# Digital_Clock_SCH_4_0.net
KiCad netlist of a schematic drawn in Altium Designer
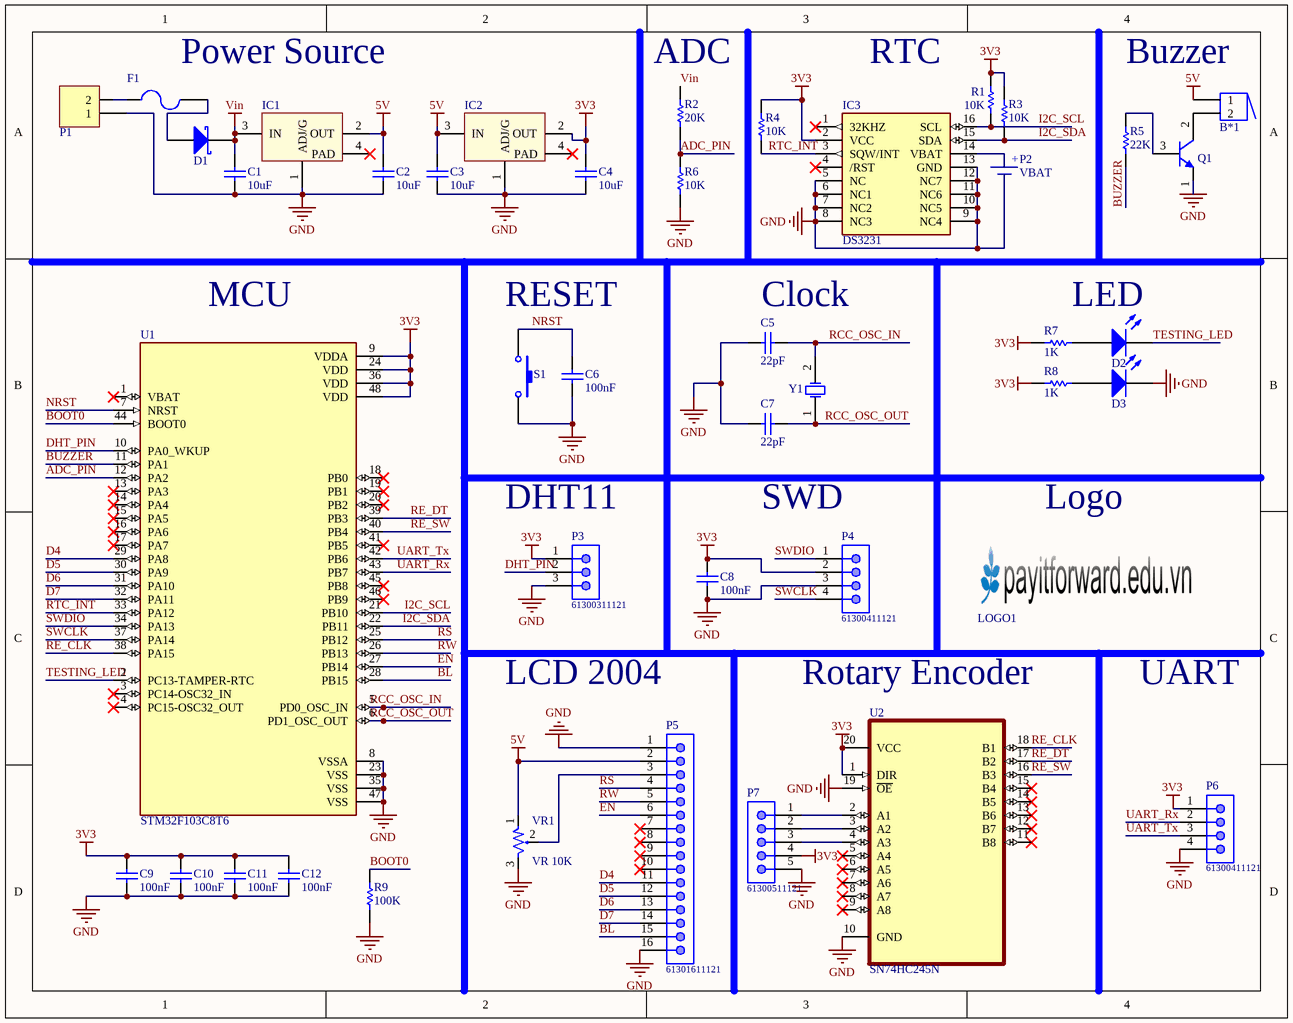
[diagram p0: Digital_Clock_SCH_4.0.SchDoc]

(export (version "E")
  (design (tool "Eeschema 10.0.6"))
  (components
    (comp (ref "B*1") (value "Buzzer") (footprint "BUZZER") (libsource (lib "PIF_Library") (part "Buzzer")))
    (comp (ref "C1")
      (value "10uF")
      (footprint "CAP-SM-0805")
      (description "Capacitor")
      (fields (field (name "Comment") "Cap Non-Pol SMD"))
      (libsource (lib "PIF_Library") (part "Cap Non-Pol SMD"))
    )
    (comp (ref "C2")
      (value "10uF")
      (footprint "CAP-SM-0805")
      (description "Capacitor")
      (fields (field (name "Comment") "Cap Non-Pol SMD"))
      (libsource (lib "PIF_Library") (part "Cap Non-Pol SMD"))
    )
    (comp (ref "C3")
      (value "10uF")
      (footprint "CAP-SM-0805")
      (description "Capacitor")
      (fields (field (name "Comment") "Cap Non-Pol SMD"))
      (libsource (lib "PIF_Library") (part "Cap Non-Pol SMD"))
    )
    (comp (ref "C4")
      (value "10uF")
      (footprint "CAP-SM-0805")
      (description "Capacitor")
      (fields (field (name "Comment") "Cap Non-Pol SMD"))
      (libsource (lib "PIF_Library") (part "Cap Non-Pol SMD"))
    )
    (comp (ref "C5")
      (value "22pF")
      (footprint "CAP-SM-0603")
      (description "Capacitor")
      (fields (field (name "Comment") "Cap Non-Pol SMD"))
      (libsource (lib "PIF_Library") (part "Cap Non-Pol SMD"))
    )
    (comp (ref "C6")
      (value "100nF")
      (footprint "CAP-SM-0603")
      (description "Capacitor")
      (fields (field (name "Comment") "Cap Non-Pol SMD"))
      (libsource (lib "PIF_Library") (part "Cap Non-Pol SMD"))
    )
    (comp (ref "C7")
      (value "22pF")
      (footprint "CAP-SM-0603")
      (description "Capacitor")
      (fields (field (name "Comment") "Cap Non-Pol SMD"))
      (libsource (lib "PIF_Library") (part "Cap Non-Pol SMD"))
    )
    (comp (ref "C8")
      (value "100nF")
      (footprint "CAP-SM-0603")
      (description "Capacitor")
      (fields (field (name "Comment") "Cap Non-Pol SMD"))
      (libsource (lib "PIF_Library") (part "Cap Non-Pol SMD"))
    )
    (comp (ref "C9")
      (value "100nF")
      (footprint "CAP-SM-0603")
      (description "Capacitor")
      (fields (field (name "Comment") "Cap Non-Pol SMD"))
      (libsource (lib "PIF_Library") (part "Cap Non-Pol SMD"))
    )
    (comp (ref "C10")
      (value "100nF")
      (footprint "CAP-SM-0603")
      (description "Capacitor")
      (fields (field (name "Comment") "Cap Non-Pol SMD"))
      (libsource (lib "PIF_Library") (part "Cap Non-Pol SMD"))
    )
    (comp (ref "C11")
      (value "100nF")
      (footprint "CAP-SM-0603")
      (description "Capacitor")
      (fields (field (name "Comment") "Cap Non-Pol SMD"))
      (libsource (lib "PIF_Library") (part "Cap Non-Pol SMD"))
    )
    (comp (ref "C12")
      (value "100nF")
      (footprint "CAP-SM-0603")
      (description "Capacitor")
      (fields (field (name "Comment") "Cap Non-Pol SMD"))
      (libsource (lib "PIF_Library") (part "Cap Non-Pol SMD"))
    )
    (comp (ref "D1")
      (value "D Schottky")
      (footprint "SS34")
      (description "Schottky Diode")
      (fields (field (name "PUBLISHER") "Altium Limited"))
      (libsource (lib "PIF_Library") (part "D Schottky"))
    )
    (comp (ref "D2")
      (value "LED SMD")
      (footprint "LED_0805_Blue")
      (description "LED")
      (libsource (lib "PIF_Library") (part "LED SMD"))
    )
    (comp (ref "D3")
      (value "LED SMD")
      (footprint "LED_0805_Blue")
      (description "LED")
      (libsource (lib "PIF_Library") (part "LED SMD"))
    )
    (comp (ref "F1") (value "Fuse") (footprint "FUSE SMD") (libsource (lib "PIF_Library") (part "Fuse")))
    (comp (ref "IC1")
      (value "LM1117")
      (footprint "SOT223-4N")
      (description "Available in 1.8V, 2.5V, 2.85V, 3.3V, 5V, and  Adjustable Versions")
      (libsource (lib "PIF_Library") (part "LM1117"))
    )
    (comp (ref "IC2")
      (value "LM1117")
      (footprint "SOT223-4N")
      (description "Available in 1.8V, 2.5V, 2.85V, 3.3V, 5V, and  Adjustable Versions")
      (libsource (lib "PIF_Library") (part "LM1117"))
    )
    (comp (ref "IC3") (value "DS3231") (footprint "SO16W") (libsource (lib "DS3231") (part "DS3231")))
    (comp (ref "LOGO1")
      (value "LOGO PIF")
      (footprint "PIF LOGO BIG SSTOP")
      (libsource (lib "PIF_Library") (part "LOGO PIF"))
    )
    (comp (ref "P1")
      (value "Domino 2")
      (footprint "DOMINO SMALL 2")
      (description "Domino, 2-Pin")
      (fields (field (name "PUBLISHER") "Altium Limited"))
      (libsource (lib "PIF_Library") (part "Domino 2"))
    )
    (comp (ref "P2")
      (value "VBAT")
      (footprint "VBAT CR2030")
      (description "CR2032")
      (fields
        (field (name "MANUFACTURER") "DANTONA INDUSTRIES")
        (field (name "MANUFACTURER PART NUMBER") "CR2032 SANYO")
      )
      (libsource (lib "DeltaCross_Lib") (part "VBAT CR2032"))
    )
    (comp (ref "P3")
      (value "61300311121")
      (footprint "61300311121")
      (description "WR-PHD Pin Header, THT, pitch 2.54mm, Single Row, Vertical, 3p")
      (fields (field (name "MANUFACTURER") "Wurth Elektronik"))
      (libsource (lib "Altium_WR-PHD (rev20a)") (part "61300311121"))
    )
    (comp (ref "P4")
      (value "61300411121")
      (footprint "61300411121")
      (description "WR-PHD Pin Header, THT, pitch 2.54mm, Single Row, Vertical, 4p")
      (fields (field (name "MANUFACTURER") "Wurth Elektronik"))
      (libsource (lib "Altium_WR-PHD (rev20a)") (part "61300411121"))
    )
    (comp (ref "P5")
      (value "61301611121")
      (footprint "61301611121")
      (description "WR-PHD Pin Header, THT, pitch 2.54mm, Single Row, Vertical, 16p")
      (fields (field (name "MANUFACTURER") "Wurth Elektronik"))
      (libsource (lib "Altium_WR-PHD (rev20a)") (part "61301611121"))
    )
    (comp (ref "P6")
      (value "61300411121")
      (footprint "61300411121")
      (description "WR-PHD Pin Header, THT, pitch 2.54mm, Single Row, Vertical, 4p")
      (fields (field (name "MANUFACTURER") "Wurth Elektronik"))
      (libsource (lib "Altium_WR-PHD (rev20a)") (part "61300411121"))
    )
    (comp (ref "P7")
      (value "61300511121")
      (footprint "61300511121")
      (description "WR-PHD Pin Header, THT, pitch 2.54mm, Single Row, Vertical, 5p")
      (fields (field (name "MANUFACTURER") "Wurth Elektronik"))
      (libsource (lib "Altium_WR-PHD (rev20a)") (part "61300511121"))
    )
    (comp (ref "Q1")
      (value "C1815")
      (footprint "SOT23B")
      (description "NPN Bipolar Transistor")
      (libsource (lib "PIF_Library") (part "C1815"))
    )
    (comp (ref "R1")
      (value "10K")
      (footprint "RES-SM-0603")
      (description "Resistor")
      (fields (field (name "Comment") "RESISTOR SMD"))
      (libsource (lib "PIF_Library") (part "RESISTOR SMD"))
    )
    (comp (ref "R2")
      (value "20K")
      (footprint "RES-SM-0603")
      (description "Resistor")
      (fields (field (name "Comment") "RESISTOR SMD"))
      (libsource (lib "PIF_Library") (part "RESISTOR SMD"))
    )
    (comp (ref "R3")
      (value "10K")
      (footprint "RES-SM-0603")
      (description "Resistor")
      (fields (field (name "Comment") "RESISTOR SMD"))
      (libsource (lib "PIF_Library") (part "RESISTOR SMD"))
    )
    (comp (ref "R4")
      (value "10K")
      (footprint "RES-SM-0603")
      (description "Resistor")
      (fields (field (name "Comment") "RESISTOR SMD"))
      (libsource (lib "PIF_Library") (part "RESISTOR SMD"))
    )
    (comp (ref "R5")
      (value "22K")
      (footprint "RES-SM-0603")
      (description "Resistor")
      (fields (field (name "Comment") "RESISTOR SMD"))
      (libsource (lib "PIF_Library") (part "RESISTOR SMD"))
    )
    (comp (ref "R6")
      (value "10K")
      (footprint "RES-SM-0603")
      (description "Resistor")
      (fields (field (name "Comment") "RESISTOR SMD"))
      (libsource (lib "PIF_Library") (part "RESISTOR SMD"))
    )
    (comp (ref "R7")
      (value "1K")
      (footprint "RES-SM-0603")
      (description "Resistor")
      (fields (field (name "Comment") "RESISTOR SMD"))
      (libsource (lib "PIF_Library") (part "RESISTOR SMD"))
    )
    (comp (ref "R8")
      (value "1K")
      (footprint "RES-SM-0603")
      (description "Resistor")
      (fields (field (name "Comment") "RESISTOR SMD"))
      (libsource (lib "PIF_Library") (part "RESISTOR SMD"))
    )
    (comp (ref "R9")
      (value "100K")
      (footprint "RES-SM-0603")
      (description "Resistor")
      (fields (field (name "Comment") "RESISTOR SMD"))
      (libsource (lib "PIF_Library") (part "RESISTOR SMD"))
    )
    (comp (ref "S1")
      (value "Tact SW - 2Pin")
      (footprint "SW-SMD")
      (description "Switch button 2 pin")
      (libsource (lib "PIF_Library") (part "Tact SW - 2Pin"))
    )
    (comp (ref "U1")
      (value "STM32F103C8T6")
      (footprint "QFP50P900X900X160-48N")
      (libsource (lib "STM32F103C8T6") (part "STM32F103C8T6"))
    )
    (comp (ref "U2")
      (value "SN74HC245N")
      (footprint "DIP254P762X508-20")
      (description "Octal Bus Transceivers With 3-State Outputs 20-PDIP -40 to 85")
      (fields (field (name "MF") "Texas Instruments"))
      (libsource (lib "SN74HC245N") (part "SN74HC245N"))
    )
    (comp (ref "VR1")
      (value "VR 10K")
      (footprint "Varistor 1")
      (description "Var Resistor")
      (fields (field (name "Comment") "10K"))
      (libsource (lib "PIF_Library") (part "Var Resistor"))
    )
    (comp (ref "Y1")
      (value "XTAL")
      (footprint "XT2")
      (description "Crystal Oscillator")
      (fields (field (name "PUBLISHER") "Altium Limited"))
      (libsource (lib "PIF_Library") (part "XTAL"))
    )
  )
  (nets
    (net (code "1") (name "/ADC_PIN") (class "Default")
      (node (ref "R2") (pin "1") (pinfunction "1_1") (pintype "passive"))
      (node (ref "R6") (pin "2") (pinfunction "2_2") (pintype "passive"))
      (node (ref "U1") (pin "12") (pinfunction "PA2_12") (pintype "bidirectional"))
    )
    (net (code "2") (name "/BL") (class "Default")
      (node (ref "P5") (pin "15") (pinfunction "15_15") (pintype "passive"))
      (node (ref "U1") (pin "28") (pinfunction "PB15_28") (pintype "bidirectional"))
    )
    (net (code "3") (name "/BOOT0") (class "Default")
      (node (ref "R9") (pin "2") (pinfunction "2_2") (pintype "passive"))
      (node (ref "U1") (pin "44") (pinfunction "BOOT0_44") (pintype "input"))
    )
    (net (code "4") (name "/BUZZER") (class "Default")
      (node (ref "R5") (pin "1") (pinfunction "1_1") (pintype "passive"))
      (node (ref "U1") (pin "11") (pinfunction "PA1_11") (pintype "bidirectional"))
    )
    (net (code "5") (name "/D4") (class "Default")
      (node (ref "P5") (pin "11") (pinfunction "11_11") (pintype "passive"))
      (node (ref "U1") (pin "29") (pinfunction "PA8_29") (pintype "bidirectional"))
    )
    (net (code "6") (name "/D5") (class "Default")
      (node (ref "P5") (pin "12") (pinfunction "12_12") (pintype "passive"))
      (node (ref "U1") (pin "30") (pinfunction "PA9_30") (pintype "bidirectional"))
    )
    (net (code "7") (name "/D6") (class "Default")
      (node (ref "P5") (pin "13") (pinfunction "13_13") (pintype "passive"))
      (node (ref "U1") (pin "31") (pinfunction "PA10_31") (pintype "bidirectional"))
    )
    (net (code "8") (name "/D7") (class "Default")
      (node (ref "P5") (pin "14") (pinfunction "14_14") (pintype "passive"))
      (node (ref "U1") (pin "32") (pinfunction "PA11_32") (pintype "bidirectional"))
    )
    (net (code "9") (name "/DHT_PIN") (class "Default")
      (node (ref "P3") (pin "2") (pinfunction "2_2") (pintype "passive"))
      (node (ref "U1") (pin "10") (pinfunction "PA0_WKUP_10") (pintype "bidirectional"))
    )
    (net (code "10") (name "/EN") (class "Default")
      (node (ref "P5") (pin "6") (pinfunction "6_6") (pintype "passive"))
      (node (ref "U1") (pin "27") (pinfunction "PB14_27") (pintype "bidirectional"))
    )
    (net (code "11") (name "/I2C_SCL") (class "Default")
      (node (ref "IC3") (pin "16") (pinfunction "SCL_16") (pintype "bidirectional"))
      (node (ref "R1") (pin "1") (pinfunction "1_1") (pintype "passive"))
      (node (ref "U1") (pin "21") (pinfunction "PB10_21") (pintype "bidirectional"))
    )
    (net (code "12") (name "/I2C_SDA") (class "Default")
      (node (ref "IC3") (pin "15") (pinfunction "SDA_15") (pintype "bidirectional"))
      (node (ref "R3") (pin "1") (pinfunction "1_1") (pintype "passive"))
      (node (ref "U1") (pin "22") (pinfunction "PB11_22") (pintype "bidirectional"))
    )
    (net (code "13") (name "/NRST") (class "Default")
      (node (ref "C6") (pin "2") (pinfunction "2_2") (pintype "passive"))
      (node (ref "S1") (pin "1") (pinfunction "1_1") (pintype "passive"))
      (node (ref "U1") (pin "7") (pinfunction "NRST_7") (pintype "input"))
    )
    (net (code "14") (name "/RCC_OSC_IN") (class "Default")
      (node (ref "C5") (pin "2") (pinfunction "2_2") (pintype "passive"))
      (node (ref "U1") (pin "5") (pinfunction "PD0_OSC_IN_5") (pintype "bidirectional"))
      (node (ref "Y1") (pin "2") (pinfunction "OSC2_2") (pintype "passive"))
    )
    (net (code "15") (name "/RCC_OSC_OUT") (class "Default")
      (node (ref "C7") (pin "1") (pinfunction "1_1") (pintype "passive"))
      (node (ref "U1") (pin "6") (pinfunction "PD1_OSC_OUT_6") (pintype "bidirectional"))
      (node (ref "Y1") (pin "1") (pinfunction "OSC1_1") (pintype "passive"))
    )
    (net (code "16") (name "/RE_CLK") (class "Default")
      (node (ref "U1") (pin "38") (pinfunction "PA15_38") (pintype "bidirectional"))
      (node (ref "U2") (pin "18") (pinfunction "B1_18") (pintype "bidirectional"))
    )
    (net (code "17") (name "/RE_DT") (class "Default")
      (node (ref "U1") (pin "39") (pinfunction "PB3_39") (pintype "bidirectional"))
      (node (ref "U2") (pin "17") (pinfunction "B2_17") (pintype "bidirectional"))
    )
    (net (code "18") (name "/RE_SW") (class "Default")
      (node (ref "U1") (pin "40") (pinfunction "PB4_40") (pintype "bidirectional"))
      (node (ref "U2") (pin "16") (pinfunction "B3_16") (pintype "bidirectional"))
    )
    (net (code "19") (name "/RS") (class "Default")
      (node (ref "P5") (pin "4") (pinfunction "4_4") (pintype "passive"))
      (node (ref "U1") (pin "25") (pinfunction "PB12_25") (pintype "bidirectional"))
    )
    (net (code "20") (name "/RTC_INT") (class "Default")
      (node (ref "IC3") (pin "3") (pinfunction "SQW/INT_3") (pintype "output"))
      (node (ref "R4") (pin "1") (pinfunction "1_1") (pintype "passive"))
      (node (ref "U1") (pin "33") (pinfunction "PA12_33") (pintype "bidirectional"))
    )
    (net (code "21") (name "/RW") (class "Default")
      (node (ref "P5") (pin "5") (pinfunction "5_5") (pintype "passive"))
      (node (ref "U1") (pin "26") (pinfunction "PB13_26") (pintype "bidirectional"))
    )
    (net (code "22") (name "/SWCLK") (class "Default")
      (node (ref "P4") (pin "4") (pinfunction "4_4") (pintype "passive"))
      (node (ref "U1") (pin "37") (pinfunction "PA14_37") (pintype "bidirectional"))
    )
    (net (code "23") (name "/SWDIO") (class "Default")
      (node (ref "P4") (pin "1") (pinfunction "1_1") (pintype "passive"))
      (node (ref "U1") (pin "34") (pinfunction "PA13_34") (pintype "bidirectional"))
    )
    (net (code "24") (name "/TESTING_LED") (class "Default")
      (node (ref "D2") (pin "2") (pinfunction "K_2") (pintype "passive"))
      (node (ref "U1") (pin "2") (pinfunction "PC13-TAMPER-RTC_2") (pintype "bidirectional"))
    )
    (net (code "25") (name "/UART_Rx") (class "Default")
      (node (ref "P6") (pin "2") (pinfunction "2_2") (pintype "passive"))
      (node (ref "U1") (pin "43") (pinfunction "PB7_43") (pintype "bidirectional"))
    )
    (net (code "26") (name "/UART_Tx") (class "Default")
      (node (ref "P6") (pin "3") (pinfunction "3_3") (pintype "passive"))
      (node (ref "U1") (pin "42") (pinfunction "PB6_42") (pintype "bidirectional"))
    )
    (net (code "27") (name "3V3") (class "Default")
      (node (ref "C10") (pin "2") (pinfunction "2_2") (pintype "passive"))
      (node (ref "C11") (pin "2") (pinfunction "2_2") (pintype "passive"))
      (node (ref "C12") (pin "2") (pinfunction "2_2") (pintype "passive"))
      (node (ref "C4") (pin "2") (pinfunction "2_2") (pintype "passive"))
      (node (ref "C8") (pin "2") (pinfunction "2_2") (pintype "passive"))
      (node (ref "C9") (pin "2") (pinfunction "2_2") (pintype "passive"))
      (node (ref "IC2") (pin "2") (pinfunction "OUT_2") (pintype "passive"))
      (node (ref "IC3") (pin "2") (pinfunction "VCC_2") (pintype "power_in"))
      (node (ref "P3") (pin "1") (pinfunction "1_1") (pintype "passive"))
      (node (ref "P4") (pin "2") (pinfunction "2_2") (pintype "passive"))
      (node (ref "P6") (pin "1") (pinfunction "1_1") (pintype "passive"))
      (node (ref "P7") (pin "4") (pinfunction "4_4") (pintype "passive"))
      (node (ref "R1") (pin "2") (pinfunction "2_2") (pintype "passive"))
      (node (ref "R3") (pin "2") (pinfunction "2_2") (pintype "passive"))
      (node (ref "R4") (pin "2") (pinfunction "2_2") (pintype "passive"))
      (node (ref "R7") (pin "1") (pinfunction "1_1") (pintype "passive"))
      (node (ref "R8") (pin "1") (pinfunction "1_1") (pintype "passive"))
      (node (ref "U1") (pin "24") (pinfunction "VDD_24") (pintype "power_in"))
      (node (ref "U1") (pin "36") (pinfunction "VDD_36") (pintype "power_in"))
      (node (ref "U1") (pin "48") (pinfunction "VDD_48") (pintype "power_in"))
      (node (ref "U1") (pin "9") (pinfunction "VDDA_9") (pintype "power_in"))
      (node (ref "U2") (pin "1") (pinfunction "DIR_1") (pintype "input"))
      (node (ref "U2") (pin "20") (pinfunction "VCC_20") (pintype "power_in"))
    )
    (net (code "28") (name "5V") (class "Default")
      (node (ref "B*1") (pin "1") (pinfunction "1_1") (pintype "passive"))
      (node (ref "C2") (pin "2") (pinfunction "2_2") (pintype "passive"))
      (node (ref "C3") (pin "2") (pinfunction "2_2") (pintype "passive"))
      (node (ref "IC1") (pin "2") (pinfunction "OUT_2") (pintype "passive"))
      (node (ref "IC2") (pin "3") (pinfunction "IN_3") (pintype "passive"))
      (node (ref "P5") (pin "2") (pinfunction "2_2") (pintype "passive"))
      (node (ref "VR1") (pin "1") (pinfunction "1_1") (pintype "passive"))
    )
    (net (code "29") (name "GND") (class "Default")
      (node (ref "C1") (pin "1") (pinfunction "1_1") (pintype "passive"))
      (node (ref "C10") (pin "1") (pinfunction "1_1") (pintype "passive"))
      (node (ref "C11") (pin "1") (pinfunction "1_1") (pintype "passive"))
      (node (ref "C12") (pin "1") (pinfunction "1_1") (pintype "passive"))
      (node (ref "C2") (pin "1") (pinfunction "1_1") (pintype "passive"))
      (node (ref "C3") (pin "1") (pinfunction "1_1") (pintype "passive"))
      (node (ref "C4") (pin "1") (pinfunction "1_1") (pintype "passive"))
      (node (ref "C5") (pin "1") (pinfunction "1_1") (pintype "passive"))
      (node (ref "C6") (pin "1") (pinfunction "1_1") (pintype "passive"))
      (node (ref "C7") (pin "2") (pinfunction "2_2") (pintype "passive"))
      (node (ref "C8") (pin "1") (pinfunction "1_1") (pintype "passive"))
      (node (ref "C9") (pin "1") (pinfunction "1_1") (pintype "passive"))
      (node (ref "D3") (pin "2") (pinfunction "K_2") (pintype "passive"))
      (node (ref "IC1") (pin "1") (pinfunction "ADJ/G_1") (pintype "passive"))
      (node (ref "IC2") (pin "1") (pinfunction "ADJ/G_1") (pintype "passive"))
      (node (ref "IC3") (pin "10") (pinfunction "NC5_10") (pintype "passive"))
      (node (ref "IC3") (pin "11") (pinfunction "NC6_11") (pintype "passive"))
      (node (ref "IC3") (pin "12") (pinfunction "NC7_12") (pintype "passive"))
      (node (ref "IC3") (pin "13") (pinfunction "GND_13") (pintype "power_in"))
      (node (ref "IC3") (pin "5") (pinfunction "NC_5") (pintype "passive"))
      (node (ref "IC3") (pin "6") (pinfunction "NC1_6") (pintype "passive"))
      (node (ref "IC3") (pin "7") (pinfunction "NC2_7") (pintype "passive"))
      (node (ref "IC3") (pin "8") (pinfunction "NC3_8") (pintype "passive"))
      (node (ref "IC3") (pin "9") (pinfunction "NC4_9") (pintype "passive"))
      (node (ref "P1") (pin "1") (pinfunction "1_1") (pintype "passive"))
      (node (ref "P2") (pin "2") (pinfunction "+_2") (pintype "passive"))
      (node (ref "P3") (pin "3") (pinfunction "3_3") (pintype "passive"))
      (node (ref "P4") (pin "3") (pinfunction "3_3") (pintype "passive"))
      (node (ref "P5") (pin "1") (pinfunction "1_1") (pintype "passive"))
      (node (ref "P5") (pin "16") (pinfunction "16_16") (pintype "passive"))
      (node (ref "P6") (pin "4") (pinfunction "4_4") (pintype "passive"))
      (node (ref "P7") (pin "5") (pinfunction "5_5") (pintype "passive"))
      (node (ref "Q1") (pin "1") (pinfunction "E_1") (pintype "passive"))
      (node (ref "R6") (pin "1") (pinfunction "1_1") (pintype "passive"))
      (node (ref "R9") (pin "1") (pinfunction "1_1") (pintype "passive"))
      (node (ref "S1") (pin "2") (pinfunction "2_2") (pintype "passive"))
      (node (ref "U1") (pin "23") (pinfunction "VSS_23") (pintype "power_in"))
      (node (ref "U1") (pin "35") (pinfunction "VSS_35") (pintype "power_in"))
      (node (ref "U1") (pin "47") (pinfunction "VSS_47") (pintype "power_in"))
      (node (ref "U1") (pin "8") (pinfunction "VSSA_8") (pintype "power_in"))
      (node (ref "U2") (pin "10") (pinfunction "GND_10") (pintype "passive"))
      (node (ref "U2") (pin "19") (pinfunction "~{OE}_19") (pintype "input"))
      (node (ref "VR1") (pin "3") (pinfunction "3_3") (pintype "passive"))
    )
    (net (code "30") (name "Net-(D1-A)") (class "Default")
      (node (ref "D1") (pin "1") (pinfunction "A_1") (pintype "passive"))
      (node (ref "F1") (pin "1") (pinfunction "1_1") (pintype "passive"))
    )
    (net (code "31") (name "Net-(D2-A)") (class "Default")
      (node (ref "D2") (pin "1") (pinfunction "A_1") (pintype "passive"))
      (node (ref "R7") (pin "2") (pinfunction "2_2") (pintype "passive"))
    )
    (net (code "32") (name "Net-(D3-A)") (class "Default")
      (node (ref "D3") (pin "1") (pinfunction "A_1") (pintype "passive"))
      (node (ref "R8") (pin "2") (pinfunction "2_2") (pintype "passive"))
    )
    (net (code "33") (name "Net-(F1-Pad2)") (class "Default")
      (node (ref "F1") (pin "2") (pinfunction "2_2") (pintype "passive"))
      (node (ref "P1") (pin "2") (pinfunction "2_2") (pintype "passive"))
    )
    (net (code "34") (name "Net-(IC3-VBAT)") (class "Default")
      (node (ref "IC3") (pin "14") (pinfunction "VBAT_14") (pintype "power_in"))
      (node (ref "P2") (pin "1") (pinfunction "+_1") (pintype "passive"))
    )
    (net (code "35") (name "Net-(P5-Pad3)") (class "Default")
      (node (ref "P5") (pin "3") (pinfunction "3_3") (pintype "passive"))
      (node (ref "VR1") (pin "2") (pinfunction "2_2") (pintype "passive"))
    )
    (net (code "36") (name "Net-(Q1-B)") (class "Default")
      (node (ref "Q1") (pin "3") (pinfunction "B_3") (pintype "passive"))
      (node (ref "R5") (pin "2") (pinfunction "2_2") (pintype "passive"))
    )
    (net (code "37") (name "Net-(Q1-C)") (class "Default")
      (node (ref "B*1") (pin "2") (pinfunction "2_2") (pintype "passive"))
      (node (ref "Q1") (pin "2") (pinfunction "C_2") (pintype "passive"))
    )
    (net (code "38") (name "Net-(U2-A1)") (class "Default")
      (node (ref "P7") (pin "1") (pinfunction "1_1") (pintype "passive"))
      (node (ref "U2") (pin "2") (pinfunction "A1_2") (pintype "bidirectional"))
    )
    (net (code "39") (name "Net-(U2-A2)") (class "Default")
      (node (ref "P7") (pin "2") (pinfunction "2_2") (pintype "passive"))
      (node (ref "U2") (pin "3") (pinfunction "A2_3") (pintype "bidirectional"))
    )
    (net (code "40") (name "Net-(U2-A3)") (class "Default")
      (node (ref "P7") (pin "3") (pinfunction "3_3") (pintype "passive"))
      (node (ref "U2") (pin "4") (pinfunction "A3_4") (pintype "bidirectional"))
    )
    (net (code "41") (name "Vin") (class "Default")
      (node (ref "C1") (pin "2") (pinfunction "2_2") (pintype "passive"))
      (node (ref "D1") (pin "2") (pinfunction "K_2") (pintype "passive"))
      (node (ref "IC1") (pin "3") (pinfunction "IN_3") (pintype "passive"))
      (node (ref "R2") (pin "2") (pinfunction "2_2") (pintype "passive"))
    )
    (net (code "42") (name "unconnected-(IC1-PAD-Pad4)") (class "Default")
      (node (ref "IC1") (pin "4") (pinfunction "PAD_4") (pintype "passive+no_connect"))
    )
    (net (code "43") (name "unconnected-(IC2-PAD-Pad4)") (class "Default")
      (node (ref "IC2") (pin "4") (pinfunction "PAD_4") (pintype "passive+no_connect"))
    )
    (net (code "44") (name "unconnected-(IC3-32KHZ-Pad1)") (class "Default")
      (node (ref "IC3") (pin "1") (pinfunction "32KHZ_1") (pintype "output+no_connect"))
    )
    (net (code "45") (name "unconnected-(IC3-{slash}RST-Pad4)") (class "Default")
      (node (ref "IC3") (pin "4") (pinfunction "/RST_4") (pintype "passive+no_connect"))
    )
    (net (code "46") (name "unconnected-(P5-Pad7)") (class "Default")
      (node (ref "P5") (pin "7") (pinfunction "7_7") (pintype "passive+no_connect"))
    )
    (net (code "47") (name "unconnected-(P5-Pad8)") (class "Default")
      (node (ref "P5") (pin "8") (pinfunction "8_8") (pintype "passive+no_connect"))
    )
    (net (code "48") (name "unconnected-(P5-Pad9)") (class "Default")
      (node (ref "P5") (pin "9") (pinfunction "9_9") (pintype "passive+no_connect"))
    )
    (net (code "49") (name "unconnected-(P5-Pad10)") (class "Default")
      (node (ref "P5") (pin "10") (pinfunction "10_10") (pintype "passive+no_connect"))
    )
    (net (code "50") (name "unconnected-(U1-PA3-Pad13)") (class "Default")
      (node (ref "U1") (pin "13") (pinfunction "PA3_13") (pintype "bidirectional+no_connect"))
    )
    (net (code "51") (name "unconnected-(U1-PA4-Pad14)") (class "Default")
      (node (ref "U1") (pin "14") (pinfunction "PA4_14") (pintype "bidirectional+no_connect"))
    )
    (net (code "52") (name "unconnected-(U1-PA5-Pad15)") (class "Default")
      (node (ref "U1") (pin "15") (pinfunction "PA5_15") (pintype "bidirectional+no_connect"))
    )
    (net (code "53") (name "unconnected-(U1-PA6-Pad16)") (class "Default")
      (node (ref "U1") (pin "16") (pinfunction "PA6_16") (pintype "bidirectional+no_connect"))
    )
    (net (code "54") (name "unconnected-(U1-PA7-Pad17)") (class "Default")
      (node (ref "U1") (pin "17") (pinfunction "PA7_17") (pintype "bidirectional+no_connect"))
    )
    (net (code "55") (name "unconnected-(U1-PB0-Pad18)") (class "Default")
      (node (ref "U1") (pin "18") (pinfunction "PB0_18") (pintype "bidirectional+no_connect"))
    )
    (net (code "56") (name "unconnected-(U1-PB1-Pad19)") (class "Default")
      (node (ref "U1") (pin "19") (pinfunction "PB1_19") (pintype "bidirectional+no_connect"))
    )
    (net (code "57") (name "unconnected-(U1-PB2-Pad20)") (class "Default")
      (node (ref "U1") (pin "20") (pinfunction "PB2_20") (pintype "bidirectional+no_connect"))
    )
    (net (code "58") (name "unconnected-(U1-PB5-Pad41)") (class "Default")
      (node (ref "U1") (pin "41") (pinfunction "PB5_41") (pintype "bidirectional+no_connect"))
    )
    (net (code "59") (name "unconnected-(U1-PB8-Pad45)") (class "Default")
      (node (ref "U1") (pin "45") (pinfunction "PB8_45") (pintype "bidirectional+no_connect"))
    )
    (net (code "60") (name "unconnected-(U1-PB9-Pad46)") (class "Default")
      (node (ref "U1") (pin "46") (pinfunction "PB9_46") (pintype "bidirectional+no_connect"))
    )
    (net (code "61") (name "unconnected-(U1-PC14-OSC32_IN-Pad3)") (class "Default")
      (node (ref "U1") (pin "3") (pinfunction "PC14-OSC32_IN_3") (pintype "bidirectional+no_connect"))
    )
    (net (code "62") (name "unconnected-(U1-PC15-OSC32_OUT-Pad4)") (class "Default")
      (node (ref "U1") (pin "4") (pinfunction "PC15-OSC32_OUT_4") (pintype "bidirectional+no_connect"))
    )
    (net (code "63") (name "unconnected-(U1-VBAT-Pad1)") (class "Default")
      (node (ref "U1") (pin "1") (pinfunction "VBAT_1") (pintype "bidirectional+no_connect"))
    )
    (net (code "64") (name "unconnected-(U2-A4-Pad5)") (class "Default")
      (node (ref "U2") (pin "5") (pinfunction "A4_5") (pintype "bidirectional+no_connect"))
    )
    (net (code "65") (name "unconnected-(U2-A5-Pad6)") (class "Default")
      (node (ref "U2") (pin "6") (pinfunction "A5_6") (pintype "bidirectional+no_connect"))
    )
    (net (code "66") (name "unconnected-(U2-A6-Pad7)") (class "Default")
      (node (ref "U2") (pin "7") (pinfunction "A6_7") (pintype "bidirectional+no_connect"))
    )
    (net (code "67") (name "unconnected-(U2-A7-Pad8)") (class "Default")
      (node (ref "U2") (pin "8") (pinfunction "A7_8") (pintype "bidirectional+no_connect"))
    )
    (net (code "68") (name "unconnected-(U2-A8-Pad9)") (class "Default")
      (node (ref "U2") (pin "9") (pinfunction "A8_9") (pintype "bidirectional+no_connect"))
    )
    (net (code "69") (name "unconnected-(U2-B4-Pad15)") (class "Default")
      (node (ref "U2") (pin "15") (pinfunction "B4_15") (pintype "bidirectional+no_connect"))
    )
    (net (code "70") (name "unconnected-(U2-B5-Pad14)") (class "Default")
      (node (ref "U2") (pin "14") (pinfunction "B5_14") (pintype "bidirectional+no_connect"))
    )
    (net (code "71") (name "unconnected-(U2-B6-Pad13)") (class "Default")
      (node (ref "U2") (pin "13") (pinfunction "B6_13") (pintype "bidirectional+no_connect"))
    )
    (net (code "72") (name "unconnected-(U2-B7-Pad12)") (class "Default")
      (node (ref "U2") (pin "12") (pinfunction "B7_12") (pintype "bidirectional+no_connect"))
    )
    (net (code "73") (name "unconnected-(U2-B8-Pad11)") (class "Default")
      (node (ref "U2") (pin "11") (pinfunction "B8_11") (pintype "bidirectional+no_connect"))
    )
  )
)
